# Adafruit_PowerBoost_1000C_Rev_B.net
KiCad netlist of a schematic drawn in Altium Designer
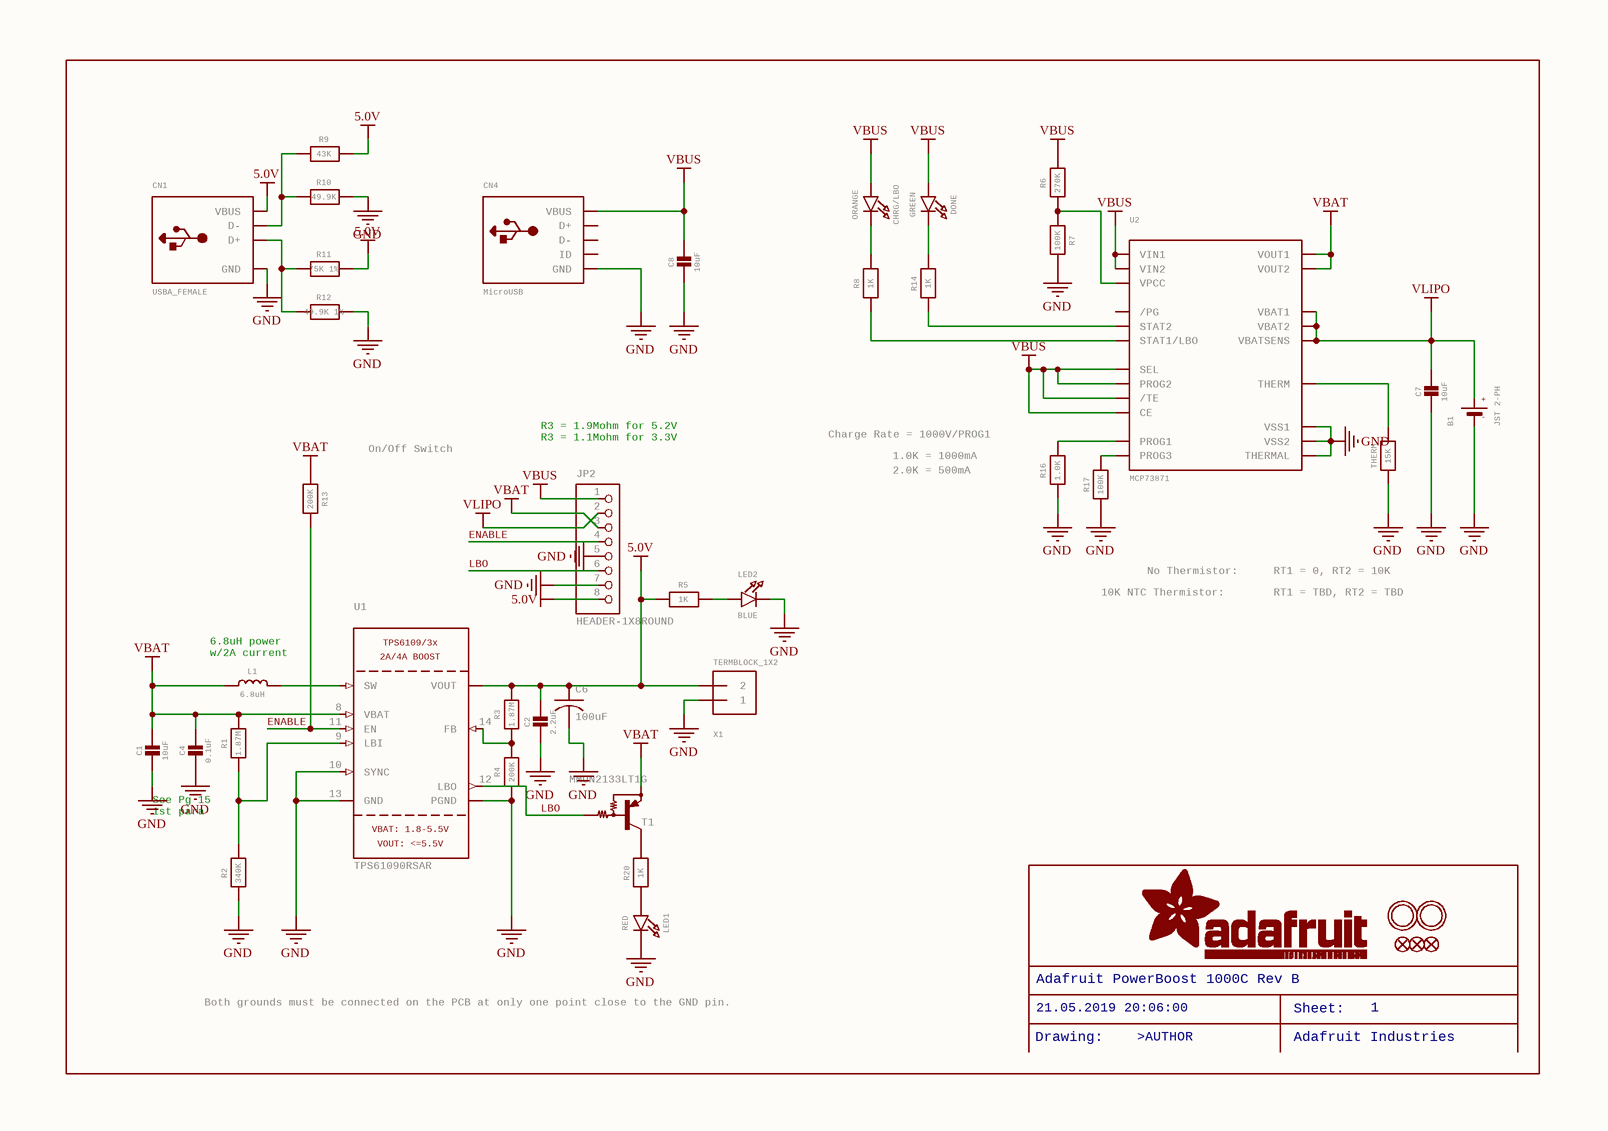
[diagram p0: Adafruit PowerBoost 1000C Rev B.SchDoc]

(export (version "E")
  (design (tool "Eeschema 10.0.6"))
  (components
    (comp (ref "B1")
      (value "JST 2-PH")
      (footprint "JSTPH2")
      (description "CR1220 SMT - Digikey: 3001K-ND  CD2032 BAT-HLD-001 - Digikey: BAT-HLD-001-ND")
      (fields (field (name "+") "+") (field (name "-") "-"))
      (libsource (lib "microbuilder") (part "BATTERY"))
    )
    (comp (ref "C1")
      (value "10uF")
      (footprint "0805-NO")
      (libsource (lib "microbuilder") (part "CAP_CERAMIC0805-NOOUTLINE"))
    )
    (comp (ref "C2")
      (value "2.2uF")
      (footprint "0805-NO")
      (libsource (lib "microbuilder") (part "CAP_CERAMIC0805-NOOUTLINE"))
    )
    (comp (ref "C4")
      (value "0.1uF")
      (footprint "0805_10MGAP")
      (libsource (lib "microbuilder") (part "CAP_CERAMIC0805_10MGAP"))
    )
    (comp (ref "C6")
      (value "100uF")
      (footprint "C1210")
      (description "CAPACITOR, American symbol")
      (libsource (lib "rcl") (part "C-USC1210"))
    )
    (comp (ref "C7")
      (value "10uF")
      (footprint "0805-NO")
      (libsource (lib "microbuilder") (part "CAP_CERAMIC0805-NOOUTLINE"))
    )
    (comp (ref "C8")
      (value "10uF")
      (footprint "0805-NO")
      (libsource (lib "microbuilder") (part "CAP_CERAMIC0805-NOOUTLINE"))
    )
    (comp (ref "CHRG/LBO")
      (value "ORANGE")
      (footprint "CHIPLED_0805_NOOUTLINE")
      (libsource (lib "") (part "LED0805_NOOUTLINE_1"))
    )
    (comp (ref "CN1")
      (value "USBA_FEMALE")
      (footprint "USB_HOST-PTH")
      (libsource (lib "microbuilder") (part "USB_TYPEAPTHFML"))
    )
    (comp (ref "CN4")
      (value "MicroUSB")
      (footprint "4UCONN_20329")
      (description "USB ConnectorsUSBMINIB - Surface Mount Female Mini-B USB Connector    4UConnector: 06564")
      (libsource (lib "microbuilder") (part "USBMICRO_20329"))
    )
    (comp (ref "DONE")
      (value "GREEN")
      (footprint "CHIPLED_0805_NOOUTLINE")
      (libsource (lib "") (part "LED0805_NOOUTLINE_1"))
    )
    (comp (ref "FID1")
      (value "FIDUCIAL\"\"")
      (footprint "FIDUCIAL_1MM")
      (description "Fiducial Alignment Points   Various fiducial points for machine vision alignment.")
      (libsource (lib "microbuilder") (part "FIDUCIAL{dblquote}{dblquote}"))
    )
    (comp (ref "FID2")
      (value "FIDUCIAL\"\"")
      (footprint "FIDUCIAL_1MM")
      (description "Fiducial Alignment Points   Various fiducial points for machine vision alignment.")
      (libsource (lib "microbuilder") (part "FIDUCIAL{dblquote}{dblquote}"))
    )
    (comp (ref "FID3")
      (value "FIDUCIAL\"\"")
      (footprint "FIDUCIAL_1MM")
      (description "Fiducial Alignment Points   Various fiducial points for machine vision alignment.")
      (libsource (lib "microbuilder") (part "FIDUCIAL{dblquote}{dblquote}"))
    )
    (comp (ref "JP2")
      (value "HEADER-1X8ROUND")
      (footprint "1X08_ROUND")
      (description "PIN HEADER")
      (libsource (lib "microbuilder") (part "HEADER-1X8ROUND"))
    )
    (comp (ref "L1")
      (value "6.8uH")
      (footprint "INDUCTOR_5X5MM_TDK_VLC5045")
      (libsource (lib "microbuilder") (part "INDUCTORTDK_VLC5045"))
    )
    (comp (ref "LED1")
      (value "RED")
      (footprint "CHIPLED_0805_NOOUTLINE")
      (libsource (lib "") (part "LED0805_NOOUTLINE_1"))
    )
    (comp (ref "LED2")
      (value "BLUE")
      (footprint "CHIPLED_0805_NOOUTLINE")
      (libsource (lib "microbuilder") (part "LED0805_NOOUTLINE"))
    )
    (comp (ref "R1")
      (value "1.87M")
      (footprint "_0805MP")
      (libsource (lib "microbuilder") (part "RESISTOR_0805MP"))
    )
    (comp (ref "R2")
      (value "340K")
      (footprint "_0805MP")
      (libsource (lib "microbuilder") (part "RESISTOR_0805MP"))
    )
    (comp (ref "R3")
      (value "1.87M")
      (footprint "0805-NO")
      (libsource (lib "microbuilder") (part "RESISTOR0805_NOOUTLINE"))
    )
    (comp (ref "R4")
      (value "200K")
      (footprint "0805-NO")
      (libsource (lib "microbuilder") (part "RESISTOR0805_NOOUTLINE"))
    )
    (comp (ref "R5")
      (value "1K")
      (footprint "0805-NO")
      (libsource (lib "microbuilder") (part "RESISTOR0805_NOOUTLINE"))
    )
    (comp (ref "R6")
      (value "270K")
      (footprint "0805-NO")
      (libsource (lib "microbuilder") (part "RESISTOR0805_NOOUTLINE"))
    )
    (comp (ref "R7")
      (value "100K")
      (footprint "0805-NO")
      (libsource (lib "microbuilder") (part "RESISTOR0805_NOOUTLINE"))
    )
    (comp (ref "R8")
      (value "1K")
      (footprint "0805-NO")
      (libsource (lib "microbuilder") (part "RESISTOR0805_NOOUTLINE"))
    )
    (comp (ref "R9")
      (value "43K")
      (footprint "0805-NO")
      (libsource (lib "microbuilder") (part "RESISTOR0805_NOOUTLINE"))
    )
    (comp (ref "R10")
      (value "49.9K")
      (footprint "0805-NO")
      (libsource (lib "microbuilder") (part "RESISTOR0805_NOOUTLINE"))
    )
    (comp (ref "R11")
      (value "75K 1%")
      (footprint "0805-NO")
      (libsource (lib "microbuilder") (part "RESISTOR0805_NOOUTLINE"))
    )
    (comp (ref "R12")
      (value "49.9K 1%")
      (footprint "0805-NO")
      (libsource (lib "microbuilder") (part "RESISTOR0805_NOOUTLINE"))
    )
    (comp (ref "R13")
      (value "200K")
      (footprint "0805-NO")
      (libsource (lib "microbuilder") (part "RESISTOR0805_NOOUTLINE"))
    )
    (comp (ref "R14")
      (value "1K")
      (footprint "0805-NO")
      (libsource (lib "microbuilder") (part "RESISTOR0805_NOOUTLINE"))
    )
    (comp (ref "R16")
      (value "1.0K")
      (footprint "0805-NO")
      (libsource (lib "microbuilder") (part "RESISTOR0805_NOOUTLINE"))
    )
    (comp (ref "R17")
      (value "100K")
      (footprint "0805-NO")
      (libsource (lib "microbuilder") (part "RESISTOR0805_NOOUTLINE"))
    )
    (comp (ref "R20")
      (value "1K")
      (footprint "0805-NO")
      (libsource (lib "microbuilder") (part "RESISTOR0805_NOOUTLINE"))
    )
    (comp (ref "T1")
      (value "MMUN2133LT1G")
      (footprint "SC59-BEC")
      (description "PNP Bias Resistor Transistor")
      (libsource (lib "transistor") (part "*-PNP_DRIVER-SC59-BEC"))
    )
    (comp (ref "THERM")
      (value "15K")
      (footprint "0805-NO")
      (libsource (lib "microbuilder") (part "RESISTOR0805_NOOUTLINE"))
    )
    (comp (ref "U$10")
      (value "MOUNTINGHOLE2.5")
      (footprint "MOUNTINGHOLE_2.5_PLATED")
      (description "Mounting Hole   For #2 screws (0.086\"/2.18mm width, 0.094\"/2.4mm hole) use 2.5mm")
      (libsource (lib "microbuilder") (part "MOUNTINGHOLE2.5"))
    )
    (comp (ref "U$11")
      (value "MOUNTINGHOLE2.5")
      (footprint "MOUNTINGHOLE_2.5_PLATED")
      (description "Mounting Hole   For #2 screws (0.086\"/2.18mm width, 0.094\"/2.4mm hole) use 2.5mm")
      (libsource (lib "microbuilder") (part "MOUNTINGHOLE2.5"))
    )
    (comp (ref "U1")
      (value "TPS61090RSAR")
      (footprint "PVQFN-16")
      (description "TPS6103x 4A Boost - 1.8-5.5V Input, Adjustable Output to 5.5V")
      (fields
        (field (name "TPS6109/3X") "TPS6109/3x")
        (field (name "2A/4ABOOST") "2A/4A BOOST")
        (field (name "VBAT:1.8-5.5V") "VBAT: 1.8-5.5V")
        (field (name "VOUT:<=5.5V") "VOUT: <=5.5V")
      )
      (libsource (lib "microbuilder") (part "VREG_TPS6103X"))
    )
    (comp (ref "U2")
      (value "MCP73871")
      (footprint "QFN20_4MM")
      (description "MCP73871 Lithium Polymer Battery Charger   Digikey: MCP73871-2CCI/ML-ND")
      (libsource (lib "microbuilder") (part "MCP73871"))
    )
    (comp (ref "X1")
      (value "TERMBLOCK_1X2")
      (footprint "TERMBLOCK_1X2-3.5MM")
      (description "3.5mm Terminal block    http://www.ladyada.net/library/pcb/eaglelibrary.html")
      (libsource (lib "microbuilder") (part "TERMBLOCK_1X2"))
    )
  )
  (nets
    (net (code "1") (name "/ENABLE") (class "Default")
      (node (ref "JP2") (pin "4") (pinfunction "4_4") (pintype "passive"))
      (node (ref "R13") (pin "2") (pinfunction "2_2") (pintype "passive"))
      (node (ref "U1") (pin "11") (pinfunction "EN_11") (pintype "input"))
    )
    (net (code "2") (name "/LBO") (class "Default")
      (node (ref "JP2") (pin "6") (pinfunction "6_6") (pintype "passive"))
      (node (ref "T1") (pin "B") (pinfunction "B_B") (pintype "passive"))
      (node (ref "U1") (pin "12") (pinfunction "LBO_12") (pintype "output"))
    )
    (net (code "3") (name "5.0V") (class "Default")
      (node (ref "C2") (pin "1") (pinfunction "1_1") (pintype "passive"))
      (node (ref "C6") (pin "1") (pinfunction "1_1") (pintype "passive"))
      (node (ref "CN1") (pin "VBUS") (pinfunction "VBUS_VBUS") (pintype "power_in"))
      (node (ref "JP2") (pin "8") (pinfunction "8_8") (pintype "passive"))
      (node (ref "R11") (pin "2") (pinfunction "2_2") (pintype "passive"))
      (node (ref "R3") (pin "2") (pinfunction "2_2") (pintype "passive"))
      (node (ref "R5") (pin "1") (pinfunction "1_1") (pintype "passive"))
      (node (ref "R9") (pin "2") (pinfunction "2_2") (pintype "passive"))
      (node (ref "U1") (pin "1_15_16") (pinfunction "VOUT_1_15_16") (pintype "power_in"))
      (node (ref "X1") (pin "2") (pinfunction "2_2") (pintype "passive"))
    )
    (net (code "4") (name "GND") (class "Default")
      (node (ref "B1") (pin "1") (pinfunction "-_1") (pintype "passive"))
      (node (ref "C1") (pin "2") (pinfunction "2_2") (pintype "passive"))
      (node (ref "C2") (pin "2") (pinfunction "2_2") (pintype "passive"))
      (node (ref "C4") (pin "2") (pinfunction "2_2") (pintype "passive"))
      (node (ref "C6") (pin "2") (pinfunction "2_2") (pintype "passive"))
      (node (ref "C7") (pin "2") (pinfunction "2_2") (pintype "passive"))
      (node (ref "C8") (pin "2") (pinfunction "2_2") (pintype "passive"))
      (node (ref "CN1") (pin "GND") (pinfunction "GND_GND") (pintype "power_in"))
      (node (ref "CN4") (pin "BASE@1_BASE@2_GND_SPRT@1_SPRT@2_SPRT@3_SPRT@4") (pinfunction "GND_BASE@1_BASE@2_GND_SPRT@1_SPRT@2_SPRT@3_SPRT@4") (pintype "power_in"))
      (node (ref "JP2") (pin "5") (pinfunction "5_5") (pintype "passive"))
      (node (ref "JP2") (pin "7") (pinfunction "7_7") (pintype "passive"))
      (node (ref "LED1") (pin "C") (pinfunction "C_C") (pintype "passive"))
      (node (ref "LED2") (pin "C") (pinfunction "C_C") (pintype "passive"))
      (node (ref "R10") (pin "2") (pinfunction "2_2") (pintype "passive"))
      (node (ref "R12") (pin "2") (pinfunction "2_2") (pintype "passive"))
      (node (ref "R16") (pin "1") (pinfunction "1_1") (pintype "passive"))
      (node (ref "R17") (pin "1") (pinfunction "1_1") (pintype "passive"))
      (node (ref "R2") (pin "1") (pinfunction "1_1") (pintype "passive"))
      (node (ref "R4") (pin "1") (pinfunction "1_1") (pintype "passive"))
      (node (ref "R7") (pin "2") (pinfunction "2_2") (pintype "passive"))
      (node (ref "THERM") (pin "1") (pinfunction "1_1") (pintype "passive"))
      (node (ref "U1") (pin "10") (pinfunction "SYNC_10") (pintype "input"))
      (node (ref "U1") (pin "13") (pinfunction "GND_13") (pintype "power_in"))
      (node (ref "U1") (pin "5_6_7_P$18_P$19_P$20_P$21_P$22_THERMAL") (pinfunction "PGND_5_6_7_P$18_P$19_P$20_P$21_P$22_THERMAL") (pintype "power_in"))
      (node (ref "U2") (pin "P$10") (pinfunction "VSS1_P$10") (pintype "bidirectional"))
      (node (ref "U2") (pin "P$11") (pinfunction "VSS2_P$11") (pintype "bidirectional"))
      (node (ref "U2") (pin "P$21") (pinfunction "THERMAL_P$21") (pintype "bidirectional"))
      (node (ref "X1") (pin "1") (pinfunction "1_1") (pintype "passive"))
    )
    (net (code "5") (name "Net-(CHRG/LBO-PadC)") (class "Default")
      (node (ref "CHRG/LBO") (pin "C") (pinfunction "C_C") (pintype "passive"))
      (node (ref "R8") (pin "2") (pinfunction "2_2") (pintype "passive"))
    )
    (net (code "6") (name "Net-(CN1-PadD+)") (class "Default")
      (node (ref "CN1") (pin "D+") (pinfunction "D+_D+") (pintype "bidirectional"))
      (node (ref "R11") (pin "1") (pinfunction "1_1") (pintype "passive"))
      (node (ref "R12") (pin "1") (pinfunction "1_1") (pintype "passive"))
    )
    (net (code "7") (name "Net-(CN1-PadD-)") (class "Default")
      (node (ref "CN1") (pin "D-") (pinfunction "D-_D-") (pintype "bidirectional"))
      (node (ref "R10") (pin "1") (pinfunction "1_1") (pintype "passive"))
      (node (ref "R9") (pin "1") (pinfunction "1_1") (pintype "passive"))
    )
    (net (code "8") (name "Net-(DONE-PadC)") (class "Default")
      (node (ref "DONE") (pin "C") (pinfunction "C_C") (pintype "passive"))
      (node (ref "R14") (pin "2") (pinfunction "2_2") (pintype "passive"))
    )
    (net (code "9") (name "Net-(L1-2)") (class "Default")
      (node (ref "L1") (pin "P$2") (pinfunction "2_P$2") (pintype "passive"))
      (node (ref "U1") (pin "3_4") (pinfunction "SW_3_4") (pintype "input"))
    )
    (net (code "10") (name "Net-(LED1-PadA)") (class "Default")
      (node (ref "LED1") (pin "A") (pinfunction "A_A") (pintype "passive"))
      (node (ref "R20") (pin "1") (pinfunction "1_1") (pintype "passive"))
    )
    (net (code "11") (name "Net-(LED2-PadA)") (class "Default")
      (node (ref "LED2") (pin "A") (pinfunction "A_A") (pintype "passive"))
      (node (ref "R5") (pin "2") (pinfunction "2_2") (pintype "passive"))
    )
    (net (code "12") (name "Net-(R20-Pad2)") (class "Default")
      (node (ref "R20") (pin "2") (pinfunction "2_2") (pintype "passive"))
      (node (ref "T1") (pin "C") (pinfunction "C_C") (pintype "passive"))
    )
    (net (code "13") (name "Net-(U1-FB)") (class "Default")
      (node (ref "R3") (pin "1") (pinfunction "1_1") (pintype "passive"))
      (node (ref "R4") (pin "2") (pinfunction "2_2") (pintype "passive"))
      (node (ref "U1") (pin "14") (pinfunction "FB_14") (pintype "input"))
    )
    (net (code "14") (name "Net-(U1-LBI)") (class "Default")
      (node (ref "R1") (pin "1") (pinfunction "1_1") (pintype "passive"))
      (node (ref "R2") (pin "2") (pinfunction "2_2") (pintype "passive"))
      (node (ref "U1") (pin "9") (pinfunction "LBI_9") (pintype "input"))
    )
    (net (code "15") (name "Net-(U2-PROG1)") (class "Default")
      (node (ref "R16") (pin "2") (pinfunction "2_2") (pintype "passive"))
      (node (ref "U2") (pin "P$13") (pinfunction "PROG1_P$13") (pintype "bidirectional"))
    )
    (net (code "16") (name "Net-(U2-PROG3)") (class "Default")
      (node (ref "R17") (pin "2") (pinfunction "2_2") (pintype "passive"))
      (node (ref "U2") (pin "P$12") (pinfunction "PROG3_P$12") (pintype "bidirectional"))
    )
    (net (code "17") (name "Net-(U2-STAT1{slash}LBO)") (class "Default")
      (node (ref "R8") (pin "1") (pinfunction "1_1") (pintype "passive"))
      (node (ref "U2") (pin "P$8") (pinfunction "STAT1/LBO_P$8") (pintype "bidirectional"))
    )
    (net (code "18") (name "Net-(U2-STAT2)") (class "Default")
      (node (ref "R14") (pin "1") (pinfunction "1_1") (pintype "passive"))
      (node (ref "U2") (pin "P$7") (pinfunction "STAT2_P$7") (pintype "bidirectional"))
    )
    (net (code "19") (name "Net-(U2-THERM)") (class "Default")
      (node (ref "THERM") (pin "2") (pinfunction "2_2") (pintype "passive"))
      (node (ref "U2") (pin "P$5") (pinfunction "THERM_P$5") (pintype "bidirectional"))
    )
    (net (code "20") (name "Net-(U2-VPCC)") (class "Default")
      (node (ref "R6") (pin "1") (pinfunction "1_1") (pintype "passive"))
      (node (ref "R7") (pin "1") (pinfunction "1_1") (pintype "passive"))
      (node (ref "U2") (pin "P$2") (pinfunction "VPCC_P$2") (pintype "bidirectional"))
    )
    (net (code "21") (name "VBAT") (class "Default")
      (node (ref "C1") (pin "1") (pinfunction "1_1") (pintype "passive"))
      (node (ref "C4") (pin "1") (pinfunction "1_1") (pintype "passive"))
      (node (ref "JP2") (pin "3") (pinfunction "3_3") (pintype "passive"))
      (node (ref "L1") (pin "P$1") (pinfunction "1_P$1") (pintype "passive"))
      (node (ref "R1") (pin "2") (pinfunction "2_2") (pintype "passive"))
      (node (ref "R13") (pin "1") (pinfunction "1_1") (pintype "passive"))
      (node (ref "T1") (pin "E") (pinfunction "E_E") (pintype "passive"))
      (node (ref "U1") (pin "8") (pinfunction "VBAT_8") (pintype "input"))
      (node (ref "U2") (pin "P$1") (pinfunction "VOUT1_P$1") (pintype "bidirectional"))
      (node (ref "U2") (pin "P$20") (pinfunction "VOUT2_P$20") (pintype "bidirectional"))
    )
    (net (code "22") (name "VBUS") (class "Default")
      (node (ref "C8") (pin "1") (pinfunction "1_1") (pintype "passive"))
      (node (ref "CHRG/LBO") (pin "A") (pinfunction "A_A") (pintype "passive"))
      (node (ref "CN4") (pin "VBUS") (pinfunction "VBUS_VBUS") (pintype "power_in"))
      (node (ref "DONE") (pin "A") (pinfunction "A_A") (pintype "passive"))
      (node (ref "JP2") (pin "1") (pinfunction "1_1") (pintype "passive"))
      (node (ref "R6") (pin "2") (pinfunction "2_2") (pintype "passive"))
      (node (ref "U2") (pin "P$17") (pinfunction "CE_P$17") (pintype "bidirectional"))
      (node (ref "U2") (pin "P$18") (pinfunction "VIN1_P$18") (pintype "bidirectional"))
      (node (ref "U2") (pin "P$19") (pinfunction "VIN2_P$19") (pintype "bidirectional"))
      (node (ref "U2") (pin "P$3") (pinfunction "SEL_P$3") (pintype "bidirectional"))
      (node (ref "U2") (pin "P$4") (pinfunction "PROG2_P$4") (pintype "bidirectional"))
      (node (ref "U2") (pin "P$9") (pinfunction "/TE_P$9") (pintype "bidirectional"))
    )
    (net (code "23") (name "VLIPO") (class "Default")
      (node (ref "B1") (pin "2") (pinfunction "+_2") (pintype "passive"))
      (node (ref "C7") (pin "1") (pinfunction "1_1") (pintype "passive"))
      (node (ref "JP2") (pin "2") (pinfunction "2_2") (pintype "passive"))
      (node (ref "U2") (pin "P$14") (pinfunction "VBAT1_P$14") (pintype "bidirectional"))
      (node (ref "U2") (pin "P$15") (pinfunction "VBAT2_P$15") (pintype "bidirectional"))
      (node (ref "U2") (pin "P$16") (pinfunction "VBATSENS_P$16") (pintype "bidirectional"))
    )
    (net (code "24") (name "unconnected-(CN4-PadD+)") (class "Default")
      (node (ref "CN4") (pin "D+") (pinfunction "D+_D+") (pintype "bidirectional"))
    )
    (net (code "25") (name "unconnected-(CN4-PadD-)") (class "Default")
      (node (ref "CN4") (pin "D-") (pinfunction "D-_D-") (pintype "bidirectional"))
    )
    (net (code "26") (name "unconnected-(CN4-PadID)") (class "Default")
      (node (ref "CN4") (pin "ID") (pinfunction "ID_ID") (pintype "bidirectional"))
    )
    (net (code "27") (name "unconnected-(U2-{slash}PG-PadP$6)") (class "Default")
      (node (ref "U2") (pin "P$6") (pinfunction "/PG_P$6") (pintype "bidirectional"))
    )
  )
)
